# 2_byte_output.net
KiCad netlist of a schematic drawn in EAGLE
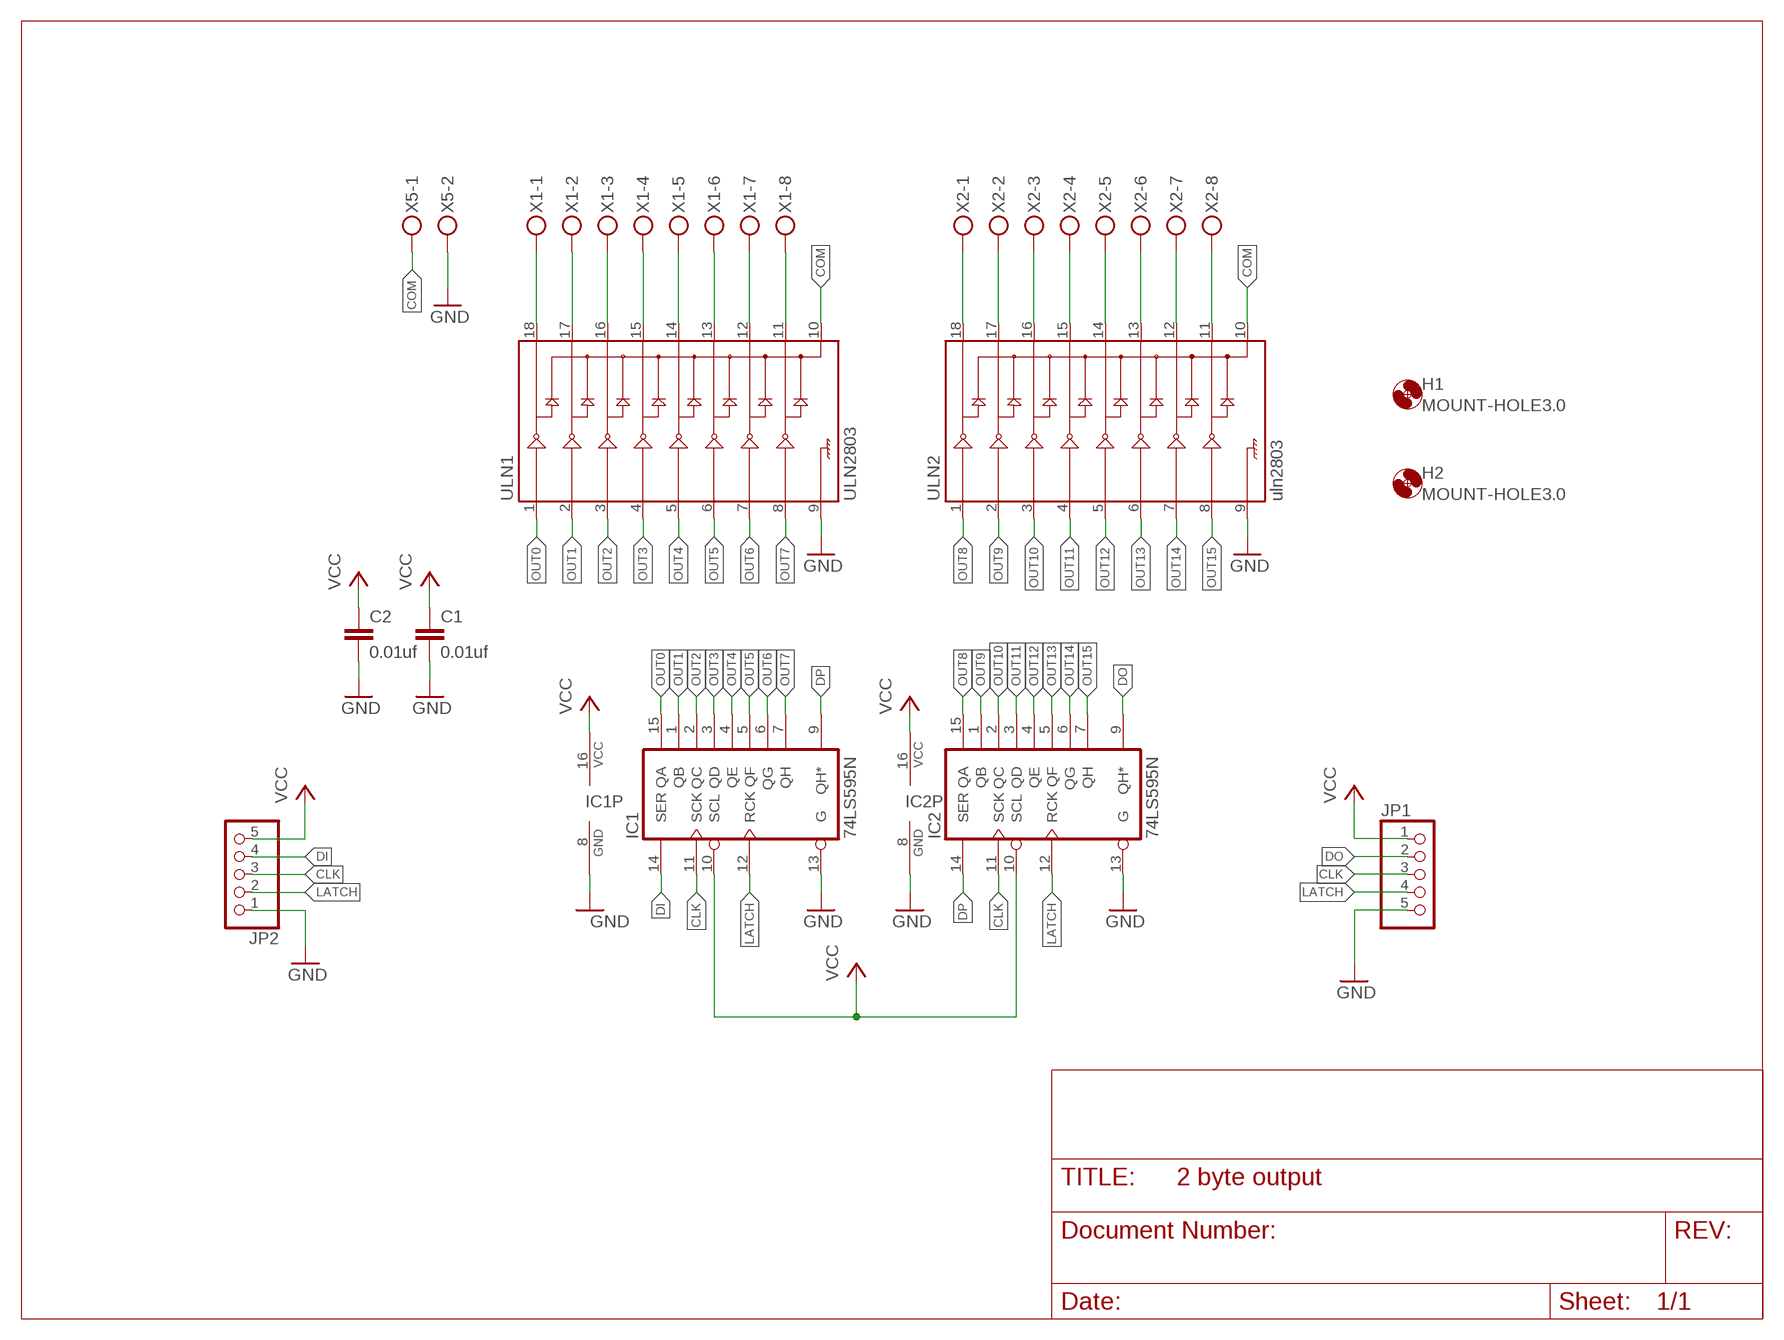
[diagram p0: schematic, sheet 1]

(export (version "E")
  (design (tool "Eeschema 10.0.6"))
  (components
    (comp (ref "C1")
      (value "0.01uf")
      (footprint "eagle-import:C050-035X075")
      (libsource (lib "eagle-import") (part "C-EU050-035X075"))
    )
    (comp (ref "C2")
      (value "0.01uf")
      (footprint "eagle-import:C050-035X075")
      (libsource (lib "eagle-import") (part "C-EU050-035X075"))
    )
    (comp (ref "H1")
      (value "MOUNT-HOLE3.0")
      (footprint "eagle-import:3,0")
      (libsource (lib "eagle-import") (part "MOUNT-HOLE3.0"))
    )
    (comp (ref "H2")
      (value "MOUNT-HOLE3.0")
      (footprint "eagle-import:3,0")
      (libsource (lib "eagle-import") (part "MOUNT-HOLE3.0"))
    )
    (comp (ref "IC1")
      (value "74LS595N")
      (footprint "eagle-import:DIL16")
      (libsource (lib "eagle-import") (part "74595NLS"))
    )
    (comp (ref "IC2")
      (value "74LS595N")
      (footprint "eagle-import:DIL16")
      (libsource (lib "eagle-import") (part "74595NLS"))
    )
    (comp (ref "JP1")
      (value "PINHD-1X5/90")
      (footprint "eagle-import:1X05_90")
      (libsource (lib "eagle-import") (part "PINHD-1X5/90"))
    )
    (comp (ref "JP2")
      (value "PINHD-1X5/90")
      (footprint "eagle-import:1X05_90")
      (libsource (lib "eagle-import") (part "PINHD-1X5/90"))
    )
    (comp (ref "ULN1")
      (value "ULN2803")
      (footprint "eagle-import:DIL18")
      (libsource (lib "eagle-import") (part "ULN2803DIP"))
    )
    (comp (ref "ULN2")
      (value "uln2803")
      (footprint "eagle-import:DIL18")
      (libsource (lib "eagle-import") (part "ULN2803DIP"))
    )
    (comp (ref "X1")
      (value "MKDSN1,5/8-5,08")
      (footprint "eagle-import:MKDSN1,5_8-5,08")
      (libsource (lib "eagle-import") (part "MKDSN1,5/8-5,08"))
    )
    (comp (ref "X2")
      (value "MKDSN1,5/8-5,08")
      (footprint "eagle-import:MKDSN1,5_8-5,08")
      (libsource (lib "eagle-import") (part "MKDSN1,5/8-5,08"))
    )
    (comp (ref "X5")
      (value "MKDSN1,5/2-5,08")
      (footprint "eagle-import:MKDSN1,5_2-5,08")
      (libsource (lib "eagle-import") (part "MKDSN1,5/2-5,08"))
    )
  )
  (nets
    (net (code "1") (name "CLK") (class "Default")
      (node (ref "IC1") (pin "11") (pinfunction "SCK_11") (pintype "input"))
      (node (ref "IC2") (pin "11") (pinfunction "SCK_11") (pintype "input"))
      (node (ref "JP1") (pin "3") (pinfunction "3_3") (pintype "passive"))
      (node (ref "JP2") (pin "3") (pinfunction "3_3") (pintype "passive"))
    )
    (net (code "2") (name "COM") (class "Default")
      (node (ref "ULN1") (pin "10") (pinfunction "10_10") (pintype "bidirectional"))
      (node (ref "ULN2") (pin "10") (pinfunction "10_10") (pintype "bidirectional"))
      (node (ref "X5") (pin "1") (pinfunction "KL_1") (pintype "passive"))
    )
    (net (code "3") (name "DI") (class "Default")
      (node (ref "IC1") (pin "14") (pinfunction "SER_14") (pintype "input"))
      (node (ref "JP2") (pin "4") (pinfunction "4_4") (pintype "passive"))
    )
    (net (code "4") (name "DO") (class "Default")
      (node (ref "IC2") (pin "9") (pinfunction "QH*_9") (pintype "tri_state"))
      (node (ref "JP1") (pin "2") (pinfunction "2_2") (pintype "passive"))
    )
    (net (code "5") (name "DP") (class "Default")
      (node (ref "IC1") (pin "9") (pinfunction "QH*_9") (pintype "tri_state"))
      (node (ref "IC2") (pin "14") (pinfunction "SER_14") (pintype "input"))
    )
    (net (code "6") (name "GND") (class "Default")
      (node (ref "C1") (pin "2") (pinfunction "2_2") (pintype "passive"))
      (node (ref "C2") (pin "2") (pinfunction "2_2") (pintype "passive"))
      (node (ref "IC1") (pin "13") (pinfunction "G_13") (pintype "input"))
      (node (ref "IC1") (pin "8") (pinfunction "GND_8") (pintype "power_in"))
      (node (ref "IC2") (pin "13") (pinfunction "G_13") (pintype "input"))
      (node (ref "IC2") (pin "8") (pinfunction "GND_8") (pintype "power_in"))
      (node (ref "JP1") (pin "5") (pinfunction "5_5") (pintype "passive"))
      (node (ref "JP2") (pin "1") (pinfunction "1_1") (pintype "passive"))
      (node (ref "ULN1") (pin "9") (pinfunction "9_9") (pintype "bidirectional"))
      (node (ref "ULN2") (pin "9") (pinfunction "9_9") (pintype "bidirectional"))
      (node (ref "X5") (pin "2") (pinfunction "KL_2") (pintype "passive"))
    )
    (net (code "7") (name "LATCH") (class "Default")
      (node (ref "IC1") (pin "12") (pinfunction "RCK_12") (pintype "input"))
      (node (ref "IC2") (pin "12") (pinfunction "RCK_12") (pintype "input"))
      (node (ref "JP1") (pin "4") (pinfunction "4_4") (pintype "passive"))
      (node (ref "JP2") (pin "2") (pinfunction "2_2") (pintype "passive"))
    )
    (net (code "8") (name "Net-(X1A-KL)") (class "Default")
      (node (ref "ULN1") (pin "18") (pinfunction "18_18") (pintype "bidirectional"))
      (node (ref "X1") (pin "1") (pinfunction "KL_1") (pintype "passive"))
    )
    (net (code "9") (name "Net-(X1B-KL)") (class "Default")
      (node (ref "ULN1") (pin "17") (pinfunction "17_17") (pintype "bidirectional"))
      (node (ref "X1") (pin "2") (pinfunction "KL_2") (pintype "passive"))
    )
    (net (code "10") (name "Net-(X1C-KL)") (class "Default")
      (node (ref "ULN1") (pin "16") (pinfunction "16_16") (pintype "bidirectional"))
      (node (ref "X1") (pin "3") (pinfunction "KL_3") (pintype "passive"))
    )
    (net (code "11") (name "Net-(X1D-KL)") (class "Default")
      (node (ref "ULN1") (pin "15") (pinfunction "15_15") (pintype "bidirectional"))
      (node (ref "X1") (pin "4") (pinfunction "KL_4") (pintype "passive"))
    )
    (net (code "12") (name "Net-(X1E-KL)") (class "Default")
      (node (ref "ULN1") (pin "14") (pinfunction "14_14") (pintype "bidirectional"))
      (node (ref "X1") (pin "5") (pinfunction "KL_5") (pintype "passive"))
    )
    (net (code "13") (name "Net-(X1F-KL)") (class "Default")
      (node (ref "ULN1") (pin "13") (pinfunction "13_13") (pintype "bidirectional"))
      (node (ref "X1") (pin "6") (pinfunction "KL_6") (pintype "passive"))
    )
    (net (code "14") (name "Net-(X1G-KL)") (class "Default")
      (node (ref "ULN1") (pin "12") (pinfunction "12_12") (pintype "bidirectional"))
      (node (ref "X1") (pin "7") (pinfunction "KL_7") (pintype "passive"))
    )
    (net (code "15") (name "Net-(X1H-KL)") (class "Default")
      (node (ref "ULN1") (pin "11") (pinfunction "11_11") (pintype "bidirectional"))
      (node (ref "X1") (pin "8") (pinfunction "KL_8") (pintype "passive"))
    )
    (net (code "16") (name "Net-(X2A-KL)") (class "Default")
      (node (ref "ULN2") (pin "18") (pinfunction "18_18") (pintype "bidirectional"))
      (node (ref "X2") (pin "1") (pinfunction "KL_1") (pintype "passive"))
    )
    (net (code "17") (name "Net-(X2B-KL)") (class "Default")
      (node (ref "ULN2") (pin "17") (pinfunction "17_17") (pintype "bidirectional"))
      (node (ref "X2") (pin "2") (pinfunction "KL_2") (pintype "passive"))
    )
    (net (code "18") (name "Net-(X2C-KL)") (class "Default")
      (node (ref "ULN2") (pin "16") (pinfunction "16_16") (pintype "bidirectional"))
      (node (ref "X2") (pin "3") (pinfunction "KL_3") (pintype "passive"))
    )
    (net (code "19") (name "Net-(X2D-KL)") (class "Default")
      (node (ref "ULN2") (pin "15") (pinfunction "15_15") (pintype "bidirectional"))
      (node (ref "X2") (pin "4") (pinfunction "KL_4") (pintype "passive"))
    )
    (net (code "20") (name "Net-(X2E-KL)") (class "Default")
      (node (ref "ULN2") (pin "14") (pinfunction "14_14") (pintype "bidirectional"))
      (node (ref "X2") (pin "5") (pinfunction "KL_5") (pintype "passive"))
    )
    (net (code "21") (name "Net-(X2F-KL)") (class "Default")
      (node (ref "ULN2") (pin "13") (pinfunction "13_13") (pintype "bidirectional"))
      (node (ref "X2") (pin "6") (pinfunction "KL_6") (pintype "passive"))
    )
    (net (code "22") (name "Net-(X2G-KL)") (class "Default")
      (node (ref "ULN2") (pin "12") (pinfunction "12_12") (pintype "bidirectional"))
      (node (ref "X2") (pin "7") (pinfunction "KL_7") (pintype "passive"))
    )
    (net (code "23") (name "Net-(X2H-KL)") (class "Default")
      (node (ref "ULN2") (pin "11") (pinfunction "11_11") (pintype "bidirectional"))
      (node (ref "X2") (pin "8") (pinfunction "KL_8") (pintype "passive"))
    )
    (net (code "24") (name "OUT0") (class "Default")
      (node (ref "IC1") (pin "15") (pinfunction "QA_15") (pintype "tri_state"))
      (node (ref "ULN1") (pin "1") (pinfunction "1_1") (pintype "bidirectional"))
    )
    (net (code "25") (name "OUT1") (class "Default")
      (node (ref "IC1") (pin "1") (pinfunction "QB_1") (pintype "tri_state"))
      (node (ref "ULN1") (pin "2") (pinfunction "2_2") (pintype "bidirectional"))
    )
    (net (code "26") (name "OUT2") (class "Default")
      (node (ref "IC1") (pin "2") (pinfunction "QC_2") (pintype "tri_state"))
      (node (ref "ULN1") (pin "3") (pinfunction "3_3") (pintype "bidirectional"))
    )
    (net (code "27") (name "OUT3") (class "Default")
      (node (ref "IC1") (pin "3") (pinfunction "QD_3") (pintype "tri_state"))
      (node (ref "ULN1") (pin "4") (pinfunction "4_4") (pintype "bidirectional"))
    )
    (net (code "28") (name "OUT4") (class "Default")
      (node (ref "IC1") (pin "4") (pinfunction "QE_4") (pintype "tri_state"))
      (node (ref "ULN1") (pin "5") (pinfunction "5_5") (pintype "bidirectional"))
    )
    (net (code "29") (name "OUT5") (class "Default")
      (node (ref "IC1") (pin "5") (pinfunction "QF_5") (pintype "tri_state"))
      (node (ref "ULN1") (pin "6") (pinfunction "6_6") (pintype "bidirectional"))
    )
    (net (code "30") (name "OUT6") (class "Default")
      (node (ref "IC1") (pin "6") (pinfunction "QG_6") (pintype "tri_state"))
      (node (ref "ULN1") (pin "7") (pinfunction "7_7") (pintype "bidirectional"))
    )
    (net (code "31") (name "OUT7") (class "Default")
      (node (ref "IC1") (pin "7") (pinfunction "QH_7") (pintype "tri_state"))
      (node (ref "ULN1") (pin "8") (pinfunction "8_8") (pintype "bidirectional"))
    )
    (net (code "32") (name "OUT8") (class "Default")
      (node (ref "IC2") (pin "15") (pinfunction "QA_15") (pintype "tri_state"))
      (node (ref "ULN2") (pin "1") (pinfunction "1_1") (pintype "bidirectional"))
    )
    (net (code "33") (name "OUT9") (class "Default")
      (node (ref "IC2") (pin "1") (pinfunction "QB_1") (pintype "tri_state"))
      (node (ref "ULN2") (pin "2") (pinfunction "2_2") (pintype "bidirectional"))
    )
    (net (code "34") (name "OUT10") (class "Default")
      (node (ref "IC2") (pin "2") (pinfunction "QC_2") (pintype "tri_state"))
      (node (ref "ULN2") (pin "3") (pinfunction "3_3") (pintype "bidirectional"))
    )
    (net (code "35") (name "OUT11") (class "Default")
      (node (ref "IC2") (pin "3") (pinfunction "QD_3") (pintype "tri_state"))
      (node (ref "ULN2") (pin "4") (pinfunction "4_4") (pintype "bidirectional"))
    )
    (net (code "36") (name "OUT12") (class "Default")
      (node (ref "IC2") (pin "4") (pinfunction "QE_4") (pintype "tri_state"))
      (node (ref "ULN2") (pin "5") (pinfunction "5_5") (pintype "bidirectional"))
    )
    (net (code "37") (name "OUT13") (class "Default")
      (node (ref "IC2") (pin "5") (pinfunction "QF_5") (pintype "tri_state"))
      (node (ref "ULN2") (pin "6") (pinfunction "6_6") (pintype "bidirectional"))
    )
    (net (code "38") (name "OUT14") (class "Default")
      (node (ref "IC2") (pin "6") (pinfunction "QG_6") (pintype "tri_state"))
      (node (ref "ULN2") (pin "7") (pinfunction "7_7") (pintype "bidirectional"))
    )
    (net (code "39") (name "OUT15") (class "Default")
      (node (ref "IC2") (pin "7") (pinfunction "QH_7") (pintype "tri_state"))
      (node (ref "ULN2") (pin "8") (pinfunction "8_8") (pintype "bidirectional"))
    )
    (net (code "40") (name "VCC") (class "Default")
      (node (ref "C1") (pin "1") (pinfunction "1_1") (pintype "passive"))
      (node (ref "C2") (pin "1") (pinfunction "1_1") (pintype "passive"))
      (node (ref "IC1") (pin "10") (pinfunction "SCL_10") (pintype "input"))
      (node (ref "IC1") (pin "16") (pinfunction "VCC_16") (pintype "power_in"))
      (node (ref "IC2") (pin "10") (pinfunction "SCL_10") (pintype "input"))
      (node (ref "IC2") (pin "16") (pinfunction "VCC_16") (pintype "power_in"))
      (node (ref "JP1") (pin "1") (pinfunction "1_1") (pintype "passive"))
      (node (ref "JP2") (pin "5") (pinfunction "5_5") (pintype "passive"))
    )
  )
)
